# placa1.net
KiCad netlist of a schematic drawn in EAGLE
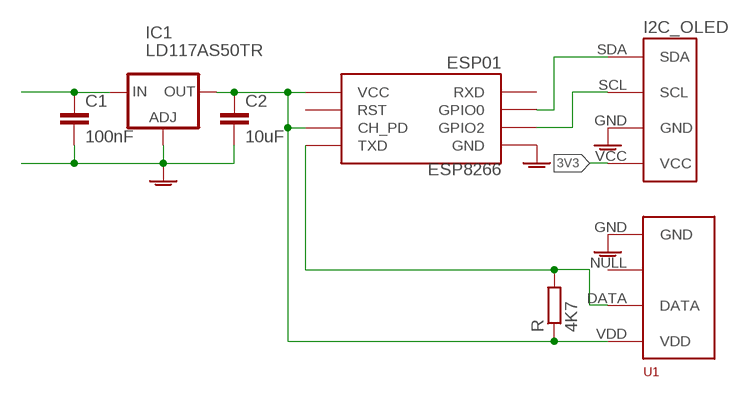
[diagram p0: schematic, sheet 1]

(export (version "E")
  (design (tool "Eeschema 10.0.6"))
  (components
    (comp (ref "C1")
      (value "100nF")
      (footprint "eagle-import:C1206K")
      (libsource (lib "eagle-import") (part "C-EUC1206K"))
    )
    (comp (ref "C2")
      (value "10uF")
      (footprint "eagle-import:C1206K")
      (libsource (lib "eagle-import") (part "C-EUC1206K"))
    )
    (comp (ref "ESP8266")
      (value "ESP01")
      (footprint "eagle-import:ESP01")
      (libsource (lib "eagle-import") (part "ESP01"))
    )
    (comp (ref "IC1")
      (value "LD117AS50TR")
      (footprint "eagle-import:SOT223")
      (libsource (lib "eagle-import") (part "LD117A?S50TR"))
    )
    (comp (ref "OLED")
      (value "I2C_OLED")
      (footprint "eagle-import:I2C_OLED_PACKAGE")
      (libsource (lib "eagle-import") (part "I2C_OLED"))
    )
    (comp (ref "R")
      (value "4K7")
      (footprint "eagle-import:R1206")
      (libsource (lib "eagle-import") (part "R-EU_R1206"))
    )
    (comp (ref "U1")
      (value "RHT03_DHT-22_AM2302RA")
      (footprint "eagle-import:RHT03_DHT-22_RA")
      (libsource (lib "eagle-import") (part "RHT03_DHT-22_AM2302RA"))
    )
  )
  (nets
    (net (code "1") (name "3V3") (class "Default")
      (node (ref "C2") (pin "1") (pinfunction "1_1") (pintype "passive"))
      (node (ref "ESP8266") (pin "CH_PD") (pinfunction "CH_PD_CH_PD") (pintype "bidirectional"))
      (node (ref "ESP8266") (pin "VCC") (pinfunction "VCC_VCC") (pintype "bidirectional"))
      (node (ref "IC1") (pin "2") (pinfunction "OUT_2") (pintype "passive"))
      (node (ref "OLED") (pin "VCC") (pinfunction "VCC_VCC") (pintype "bidirectional"))
      (node (ref "R") (pin "1") (pinfunction "1_1") (pintype "passive"))
      (node (ref "U1") (pin "VDD") (pinfunction "VDD_VDD") (pintype "power_in"))
    )
    (net (code "2") (name "GNDA") (class "Default")
      (node (ref "C1") (pin "2") (pinfunction "2_2") (pintype "passive"))
      (node (ref "C2") (pin "2") (pinfunction "2_2") (pintype "passive"))
      (node (ref "ESP8266") (pin "GND") (pinfunction "GND_GND") (pintype "bidirectional"))
      (node (ref "IC1") (pin "1") (pinfunction "ADJ_1") (pintype "input"))
      (node (ref "OLED") (pin "GND") (pinfunction "GND_GND") (pintype "bidirectional"))
      (node (ref "U1") (pin "GND") (pinfunction "GND_GND") (pintype "power_in"))
    )
    (net (code "3") (name "Net-(ESP8266-PadGPIO0)") (class "Default")
      (node (ref "ESP8266") (pin "GPIO0") (pinfunction "GPIO0_GPIO0") (pintype "bidirectional"))
      (node (ref "OLED") (pin "SDA") (pinfunction "SDA_SDA") (pintype "bidirectional"))
    )
    (net (code "4") (name "Net-(ESP8266-PadGPIO2)") (class "Default")
      (node (ref "ESP8266") (pin "GPIO2") (pinfunction "GPIO2_GPIO2") (pintype "bidirectional"))
      (node (ref "OLED") (pin "SCL") (pinfunction "SCL_SCL") (pintype "bidirectional"))
    )
    (net (code "5") (name "Net-(ESP8266-TXD)") (class "Default")
      (node (ref "ESP8266") (pin "TX") (pinfunction "TXD_TX") (pintype "bidirectional"))
      (node (ref "R") (pin "2") (pinfunction "2_2") (pintype "passive"))
      (node (ref "U1") (pin "DATA") (pinfunction "DATA_DATA") (pintype "bidirectional"))
    )
    (net (code "6") (name "Net-(IC1-IN)") (class "Default")
      (node (ref "C1") (pin "1") (pinfunction "1_1") (pintype "passive"))
      (node (ref "IC1") (pin "3") (pinfunction "IN_3") (pintype "input"))
    )
    (net (code "7") (name "unconnected-(ESP8266-PadRST)") (class "Default")
      (node (ref "ESP8266") (pin "RST") (pinfunction "RST_RST") (pintype "bidirectional"))
    )
    (net (code "8") (name "unconnected-(ESP8266-RXD-PadRX)") (class "Default")
      (node (ref "ESP8266") (pin "RX") (pinfunction "RXD_RX") (pintype "bidirectional"))
    )
    (net (code "9") (name "unconnected-(U1-PadNULL)") (class "Default")
      (node (ref "U1") (pin "NULL") (pinfunction "NULL_NULL") (pintype "no_connect"))
    )
  )
)
